# PWL_File.net
KiCad netlist of a schematic drawn in Altium Designer
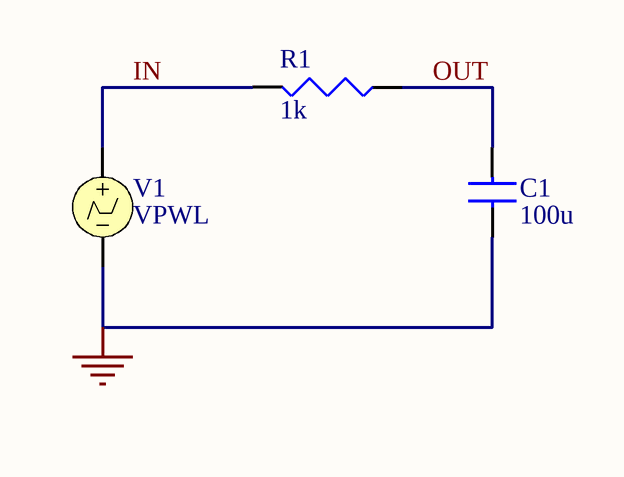
[diagram p0: PWL File.SchDoc]

(export (version "E")
  (design (tool "Eeschema 10.0.6"))
  (components
    (comp (ref "C1")
      (value "100u")
      (description "Capacitor")
      (libsource (lib "altium-import") (part "root_0_CAP_"))
    )
    (comp (ref "R1")
      (value "1k")
      (description "Resistor")
      (libsource (lib "altium-import") (part "root_1_RES_"))
    )
    (comp (ref "V1")
      (value "VPWL")
      (description "Piecewise Linear Voltage Source")
      (libsource (lib "altium-import") (part "root_0_VPWL_"))
    )
  )
  (nets
    (net (code "1") (name "/IN") (class "Default")
      (node (ref "R1") (pin "1") (pinfunction "TOP_1") (pintype "passive"))
      (node (ref "V1") (pin "1") (pinfunction "1_1") (pintype "passive"))
    )
    (net (code "2") (name "/OUT") (class "Default")
      (node (ref "C1") (pin "1") (pinfunction "1_1") (pintype "passive"))
      (node (ref "R1") (pin "2") (pinfunction "BOT_2") (pintype "passive"))
    )
    (net (code "3") (name "GND") (class "Default")
      (node (ref "C1") (pin "2") (pinfunction "2_2") (pintype "passive"))
      (node (ref "V1") (pin "2") (pinfunction "2_2") (pintype "passive"))
    )
  )
)
